# Day0_DafaFarisM_13215044.net
KiCad netlist of a schematic drawn in EAGLE
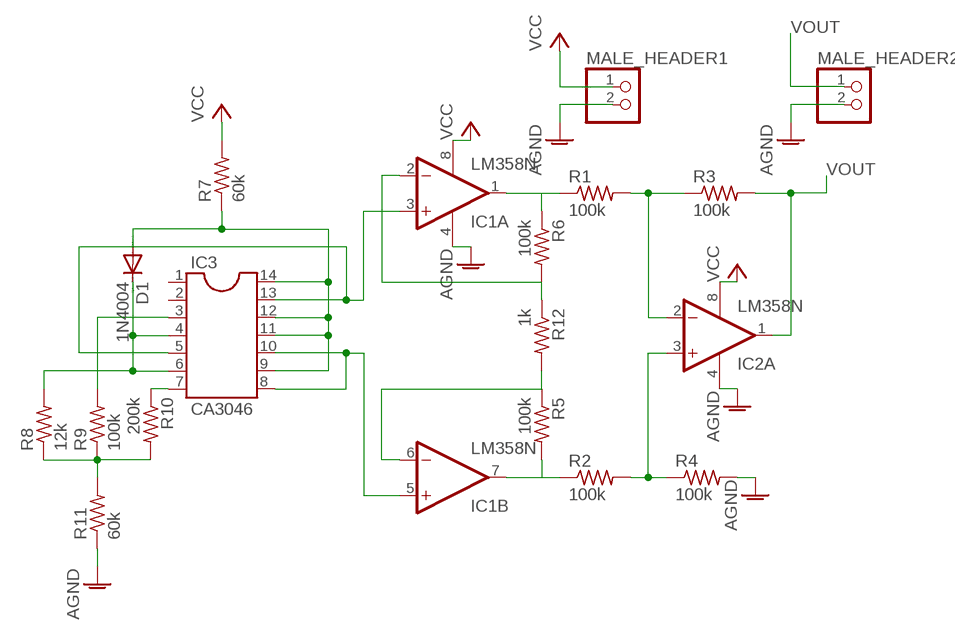
[diagram p0: schematic, sheet 1]

(export (version "E")
  (design (tool "Eeschema 10.0.6"))
  (components
    (comp (ref "D1")
      (value "1N4004")
      (footprint "eagle-import:DO41-10")
      (libsource (lib "eagle-import") (part "1N4004"))
    )
    (comp (ref "IC1")
      (value "LM358N")
      (footprint "eagle-import:DIL08")
      (libsource (lib "eagle-import") (part "LM358N"))
    )
    (comp (ref "IC2")
      (value "LM358N")
      (footprint "eagle-import:DIL08")
      (libsource (lib "eagle-import") (part "LM358N"))
    )
    (comp (ref "IC3")
      (value "CA3046")
      (footprint "eagle-import:DIL14")
      (libsource (lib "eagle-import") (part "DIL14"))
    )
    (comp (ref "MALE_HEADER1")
      (value "PINHD-1X2")
      (footprint "eagle-import:1X02")
      (libsource (lib "eagle-import") (part "PINHD-1X2"))
    )
    (comp (ref "MALE_HEADER2")
      (value "PINHD-1X2")
      (footprint "eagle-import:1X02")
      (libsource (lib "eagle-import") (part "PINHD-1X2"))
    )
    (comp (ref "R1")
      (value "100k")
      (footprint "eagle-import:0204V")
      (libsource (lib "eagle-import") (part "R-US_0204/2V"))
    )
    (comp (ref "R2")
      (value "100k")
      (footprint "eagle-import:0204V")
      (libsource (lib "eagle-import") (part "R-US_0204/2V"))
    )
    (comp (ref "R3")
      (value "100k")
      (footprint "eagle-import:0204V")
      (libsource (lib "eagle-import") (part "R-US_0204/2V"))
    )
    (comp (ref "R4")
      (value "100k")
      (footprint "eagle-import:0204V")
      (libsource (lib "eagle-import") (part "R-US_0204/2V"))
    )
    (comp (ref "R5")
      (value "100k")
      (footprint "eagle-import:0204V")
      (libsource (lib "eagle-import") (part "R-US_0204/2V"))
    )
    (comp (ref "R6")
      (value "100k")
      (footprint "eagle-import:0204V")
      (libsource (lib "eagle-import") (part "R-US_0204/2V"))
    )
    (comp (ref "R7")
      (value "60k")
      (footprint "eagle-import:0204V")
      (libsource (lib "eagle-import") (part "R-US_0204/2V"))
    )
    (comp (ref "R8")
      (value "12k")
      (footprint "eagle-import:0204V")
      (libsource (lib "eagle-import") (part "R-US_0204/2V"))
    )
    (comp (ref "R9")
      (value "100k")
      (footprint "eagle-import:0204V")
      (libsource (lib "eagle-import") (part "R-US_0204/2V"))
    )
    (comp (ref "R10")
      (value "200k")
      (footprint "eagle-import:0204V")
      (libsource (lib "eagle-import") (part "R-US_0204/2V"))
    )
    (comp (ref "R11")
      (value "60k")
      (footprint "eagle-import:0204V")
      (libsource (lib "eagle-import") (part "R-US_0204/2V"))
    )
    (comp (ref "R12")
      (value "1k")
      (footprint "eagle-import:0204V")
      (libsource (lib "eagle-import") (part "R-US_0204/2V"))
    )
  )
  (nets
    (net (code "1") (name "/VOUT") (class "Default")
      (node (ref "IC2") (pin "1") (pinfunction "OUT_1") (pintype "output"))
      (node (ref "MALE_HEADER2") (pin "1") (pinfunction "1_1") (pintype "passive"))
      (node (ref "R3") (pin "2") (pinfunction "2_2") (pintype "passive"))
    )
    (net (code "2") (name "AGND") (class "Default")
      (node (ref "IC1") (pin "4") (pinfunction "V-_4") (pintype "power_in"))
      (node (ref "IC2") (pin "4") (pinfunction "V-_4") (pintype "power_in"))
      (node (ref "MALE_HEADER1") (pin "2") (pinfunction "2_2") (pintype "passive"))
      (node (ref "MALE_HEADER2") (pin "2") (pinfunction "2_2") (pintype "passive"))
      (node (ref "R11") (pin "1") (pinfunction "1_1") (pintype "passive"))
      (node (ref "R4") (pin "2") (pinfunction "2_2") (pintype "passive"))
    )
    (net (code "3") (name "Net-(D1-PadA)") (class "Default")
      (node (ref "D1") (pin "A") (pinfunction "A_A") (pintype "passive"))
      (node (ref "IC3") (pin "11") (pinfunction "11_11") (pintype "passive"))
      (node (ref "IC3") (pin "12") (pinfunction "12_12") (pintype "passive"))
      (node (ref "IC3") (pin "14") (pinfunction "14_14") (pintype "passive"))
      (node (ref "IC3") (pin "9") (pinfunction "9_9") (pintype "passive"))
      (node (ref "R7") (pin "1") (pinfunction "1_1") (pintype "passive"))
    )
    (net (code "4") (name "Net-(D1-PadC)") (class "Default")
      (node (ref "D1") (pin "C") (pinfunction "C_C") (pintype "passive"))
      (node (ref "IC3") (pin "4") (pinfunction "4_4") (pintype "passive"))
      (node (ref "IC3") (pin "6") (pinfunction "6_6") (pintype "passive"))
      (node (ref "R8") (pin "2") (pinfunction "2_2") (pintype "passive"))
    )
    (net (code "5") (name "Net-(IC1A-+IN)") (class "Default")
      (node (ref "IC1") (pin "3") (pinfunction "+IN_3") (pintype "input"))
      (node (ref "IC3") (pin "13") (pinfunction "13_13") (pintype "passive"))
      (node (ref "IC3") (pin "5") (pinfunction "5_5") (pintype "passive"))
    )
    (net (code "6") (name "Net-(IC1A--IN)") (class "Default")
      (node (ref "IC1") (pin "2") (pinfunction "-IN_2") (pintype "input"))
      (node (ref "R12") (pin "1") (pinfunction "1_1") (pintype "passive"))
      (node (ref "R6") (pin "2") (pinfunction "2_2") (pintype "passive"))
    )
    (net (code "7") (name "Net-(IC1A-OUT)") (class "Default")
      (node (ref "IC1") (pin "1") (pinfunction "OUT_1") (pintype "output"))
      (node (ref "R1") (pin "1") (pinfunction "1_1") (pintype "passive"))
      (node (ref "R6") (pin "1") (pinfunction "1_1") (pintype "passive"))
    )
    (net (code "8") (name "Net-(IC1B-+IN)") (class "Default")
      (node (ref "IC1") (pin "5") (pinfunction "+IN_5") (pintype "input"))
      (node (ref "IC3") (pin "10") (pinfunction "10_10") (pintype "passive"))
      (node (ref "IC3") (pin "8") (pinfunction "8_8") (pintype "passive"))
    )
    (net (code "9") (name "Net-(IC1B--IN)") (class "Default")
      (node (ref "IC1") (pin "6") (pinfunction "-IN_6") (pintype "input"))
      (node (ref "R12") (pin "2") (pinfunction "2_2") (pintype "passive"))
      (node (ref "R5") (pin "1") (pinfunction "1_1") (pintype "passive"))
    )
    (net (code "10") (name "Net-(IC1B-OUT)") (class "Default")
      (node (ref "IC1") (pin "7") (pinfunction "OUT_7") (pintype "output"))
      (node (ref "R2") (pin "1") (pinfunction "1_1") (pintype "passive"))
      (node (ref "R5") (pin "2") (pinfunction "2_2") (pintype "passive"))
    )
    (net (code "11") (name "Net-(IC2A-+IN)") (class "Default")
      (node (ref "IC2") (pin "3") (pinfunction "+IN_3") (pintype "input"))
      (node (ref "R2") (pin "2") (pinfunction "2_2") (pintype "passive"))
      (node (ref "R4") (pin "1") (pinfunction "1_1") (pintype "passive"))
    )
    (net (code "12") (name "Net-(IC2A--IN)") (class "Default")
      (node (ref "IC2") (pin "2") (pinfunction "-IN_2") (pintype "input"))
      (node (ref "R1") (pin "2") (pinfunction "2_2") (pintype "passive"))
      (node (ref "R3") (pin "1") (pinfunction "1_1") (pintype "passive"))
    )
    (net (code "13") (name "Net-(IC3-Pad3)") (class "Default")
      (node (ref "IC3") (pin "3") (pinfunction "3_3") (pintype "passive"))
      (node (ref "R9") (pin "2") (pinfunction "2_2") (pintype "passive"))
    )
    (net (code "14") (name "Net-(IC3-Pad7)") (class "Default")
      (node (ref "IC3") (pin "7") (pinfunction "7_7") (pintype "passive"))
      (node (ref "R10") (pin "1") (pinfunction "1_1") (pintype "passive"))
    )
    (net (code "15") (name "Net-(R10-Pad2)") (class "Default")
      (node (ref "R10") (pin "2") (pinfunction "2_2") (pintype "passive"))
      (node (ref "R11") (pin "2") (pinfunction "2_2") (pintype "passive"))
      (node (ref "R8") (pin "1") (pinfunction "1_1") (pintype "passive"))
      (node (ref "R9") (pin "1") (pinfunction "1_1") (pintype "passive"))
    )
    (net (code "16") (name "VCC") (class "Default")
      (node (ref "IC1") (pin "8") (pinfunction "V+_8") (pintype "power_in"))
      (node (ref "IC2") (pin "8") (pinfunction "V+_8") (pintype "power_in"))
      (node (ref "MALE_HEADER1") (pin "1") (pinfunction "1_1") (pintype "passive"))
      (node (ref "R7") (pin "2") (pinfunction "2_2") (pintype "passive"))
    )
    (net (code "17") (name "unconnected-(IC3-Pad1)") (class "Default")
      (node (ref "IC3") (pin "1") (pinfunction "1_1") (pintype "passive"))
    )
    (net (code "18") (name "unconnected-(IC3-Pad2)") (class "Default")
      (node (ref "IC3") (pin "2") (pinfunction "2_2") (pintype "passive"))
    )
  )
)
